# ledterne_display.net
KiCad netlist of a schematic drawn in EAGLE
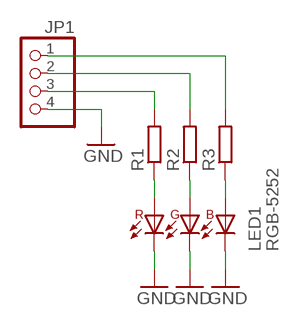
[diagram p0: schematic, sheet 1]

(export (version "E")
  (design (tool "Eeschema 10.0.6"))
  (components
    (comp (ref "JP1")
      (value "PINHD-1X4")
      (footprint "eagle-import:1X04")
      (libsource (lib "eagle-import") (part "PINHD-1X4"))
    )
    (comp (ref "LED1")
      (value "RGB-5252")
      (footprint "eagle-import:SMD_5252")
      (libsource (lib "eagle-import") (part "RGB-5252"))
    )
    (comp (ref "R1")
      (value "R-EU_R0805")
      (footprint "eagle-import:R0805")
      (libsource (lib "eagle-import") (part "R-EU_R0805"))
    )
    (comp (ref "R2")
      (value "R-EU_R0805")
      (footprint "eagle-import:R0805")
      (libsource (lib "eagle-import") (part "R-EU_R0805"))
    )
    (comp (ref "R3")
      (value "R-EU_R0805")
      (footprint "eagle-import:R0805")
      (libsource (lib "eagle-import") (part "R-EU_R0805"))
    )
  )
  (nets
    (net (code "1") (name "GND") (class "Default")
      (node (ref "JP1") (pin "4") (pinfunction "4_4") (pintype "passive"))
      (node (ref "LED1") (pin "P4") (pinfunction "CGREEN_P4") (pintype "passive"))
      (node (ref "LED1") (pin "P5") (pinfunction "CRED_P5") (pintype "passive"))
      (node (ref "LED1") (pin "P6") (pinfunction "CBLUE_P6") (pintype "passive"))
    )
    (net (code "2") (name "Net-(JP1-Pad1)") (class "Default")
      (node (ref "JP1") (pin "1") (pinfunction "1_1") (pintype "passive"))
      (node (ref "R3") (pin "2") (pinfunction "2_2") (pintype "passive"))
    )
    (net (code "3") (name "Net-(JP1-Pad2)") (class "Default")
      (node (ref "JP1") (pin "2") (pinfunction "2_2") (pintype "passive"))
      (node (ref "R2") (pin "2") (pinfunction "2_2") (pintype "passive"))
    )
    (net (code "4") (name "Net-(JP1-Pad3)") (class "Default")
      (node (ref "JP1") (pin "3") (pinfunction "3_3") (pintype "passive"))
      (node (ref "R1") (pin "2") (pinfunction "2_2") (pintype "passive"))
    )
    (net (code "5") (name "Net-(LED1-ABLUE)") (class "Default")
      (node (ref "LED1") (pin "P1") (pinfunction "ABLUE_P1") (pintype "passive"))
      (node (ref "R3") (pin "1") (pinfunction "1_1") (pintype "passive"))
    )
    (net (code "6") (name "Net-(LED1-AGREEN)") (class "Default")
      (node (ref "LED1") (pin "P3") (pinfunction "AGREEN_P3") (pintype "passive"))
      (node (ref "R2") (pin "1") (pinfunction "1_1") (pintype "passive"))
    )
    (net (code "7") (name "Net-(LED1-ARED)") (class "Default")
      (node (ref "LED1") (pin "P2") (pinfunction "ARED_P2") (pintype "passive"))
      (node (ref "R1") (pin "1") (pinfunction "1_1") (pintype "passive"))
    )
  )
)
